# NG2093_CAM_4Lane.net
KiCad netlist of a schematic drawn in Altium Designer
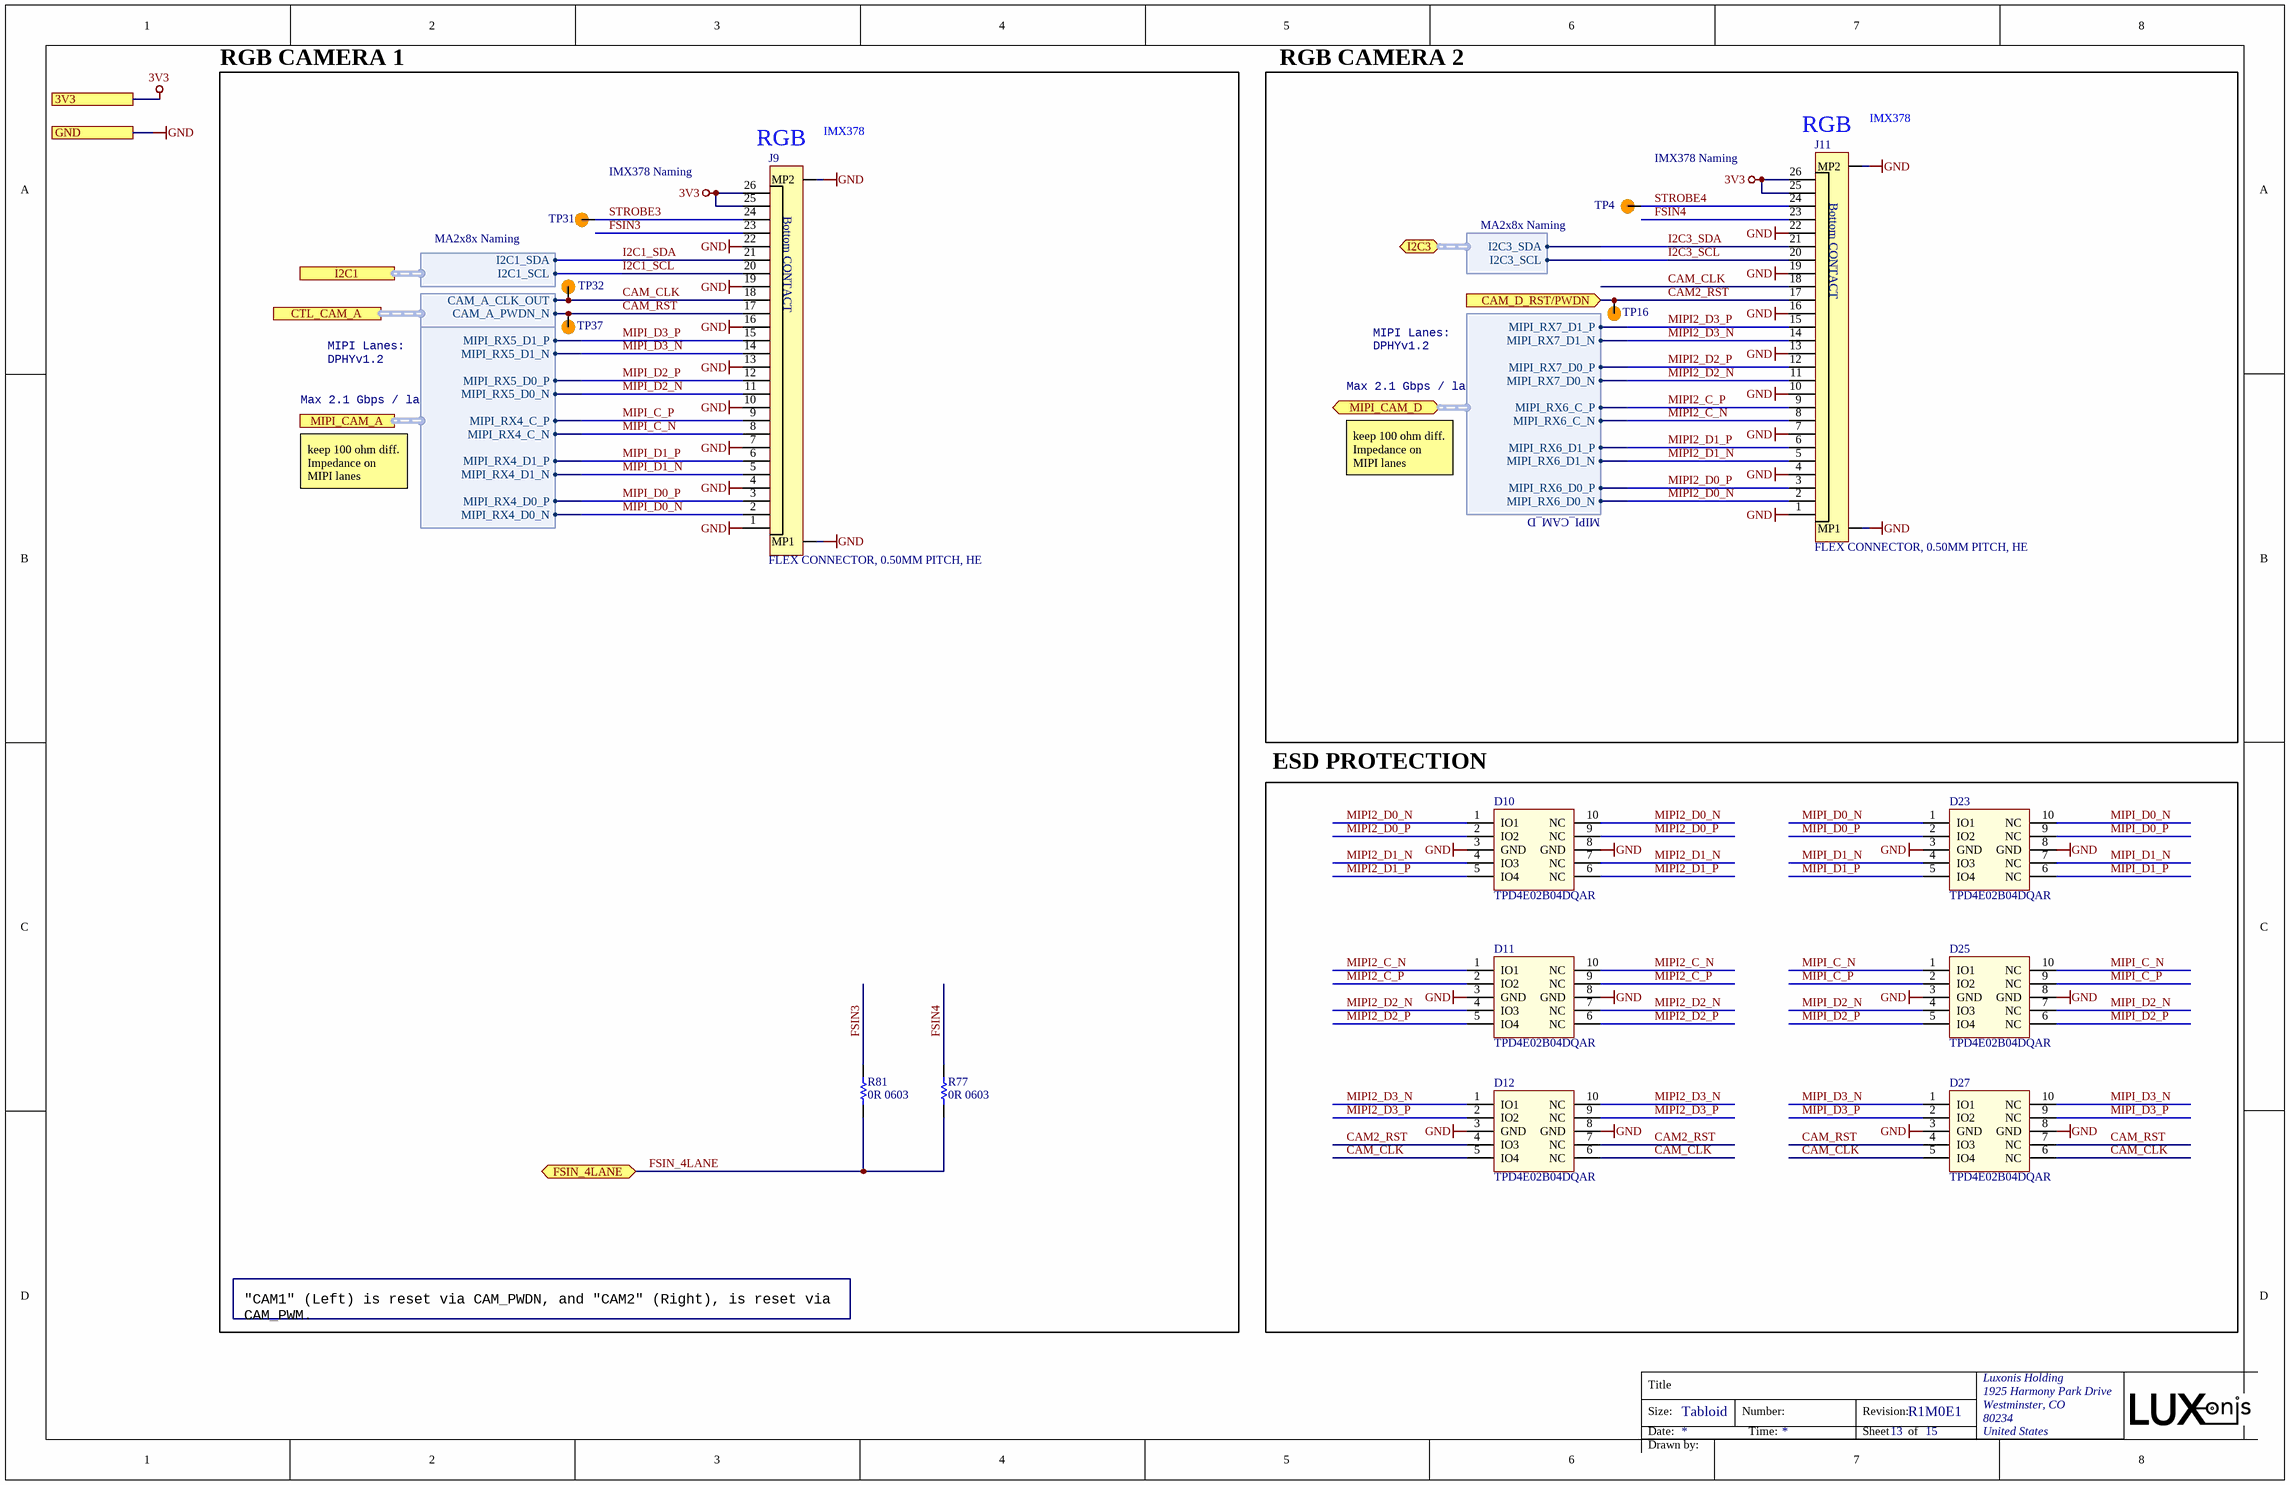
[diagram p0: NG2093_CAM_4Lane.SchDoc]

(export (version "E")
  (design (tool "Eeschema 10.0.6"))
  (components
    (comp (ref "D10")
      (value "TPD4E02B04DQAR")
      (footprint "TPD4E02B04DQAR")
      (libsource (lib "LuxonisMaster") (part "TPD4E02B04DQAR"))
    )
    (comp (ref "D11")
      (value "TPD4E02B04DQAR")
      (footprint "TPD4E02B04DQAR")
      (libsource (lib "LuxonisMaster") (part "TPD4E02B04DQAR"))
    )
    (comp (ref "D12")
      (value "TPD4E02B04DQAR")
      (footprint "TPD4E02B04DQAR")
      (libsource (lib "LuxonisMaster") (part "TPD4E02B04DQAR"))
    )
    (comp (ref "D23")
      (value "TPD4E02B04DQAR")
      (footprint "TPD4E02B04DQAR")
      (libsource (lib "LuxonisMaster") (part "TPD4E02B04DQAR"))
    )
    (comp (ref "D25")
      (value "TPD4E02B04DQAR")
      (footprint "TPD4E02B04DQAR")
      (libsource (lib "LuxonisMaster") (part "TPD4E02B04DQAR"))
    )
    (comp (ref "D27")
      (value "TPD4E02B04DQAR")
      (footprint "TPD4E02B04DQAR")
      (libsource (lib "LuxonisMaster") (part "TPD4E02B04DQAR"))
    )
    (comp (ref "J9")
      (value "FLEX CONNECTOR, 0.50MM PITCH, HE")
      (footprint "DM1090FFC:F32R-1A7H1-11026")
      (description "26 Position FFC, FPC Connector Contacts, Bottom 0.020\" (0.50mm) Surface Mount, Right Angle")
      (libsource (lib "DM1090FFC") (part "F32R-1A7H1-11026"))
    )
    (comp (ref "J11")
      (value "FLEX CONNECTOR, 0.50MM PITCH, HE")
      (footprint "DM1090FFC:F32R-1A7H1-11026")
      (description "26 Position FFC, FPC Connector Contacts, Bottom 0.020\" (0.50mm) Surface Mount, Right Angle")
      (libsource (lib "DM1090FFC") (part "F32R-1A7H1-11026"))
    )
    (comp (ref "R77")
      (value "0R 0603")
      (footprint "RESC0603(1608)_N")
      (fields (field (name "TOLERANCE") "5%"))
      (libsource (lib "LuxonisMaster") (part "CRCW06030000Z0EA"))
    )
    (comp (ref "R81")
      (value "0R 0603")
      (footprint "RESC0603(1608)_N")
      (fields (field (name "TOLERANCE") "5%"))
      (libsource (lib "LuxonisMaster") (part "CRCW06030000Z0EA"))
    )
    (comp (ref "TP4")
      (value "TP100_200_NS")
      (footprint "TP100_200_NS")
      (libsource (lib "LuxonisMaster") (part "TEST_POINT"))
    )
    (comp (ref "TP16")
      (value "TP100_200_NS")
      (footprint "TP100_200_NS")
      (libsource (lib "LuxonisMaster") (part "TEST_POINT"))
    )
    (comp (ref "TP31")
      (value "TP100_200_NS")
      (footprint "TP100_200_NS")
      (libsource (lib "LuxonisMaster") (part "TEST_POINT"))
    )
    (comp (ref "TP32")
      (value "TP100_200_NS")
      (footprint "TP100_200_NS")
      (libsource (lib "LuxonisMaster") (part "TEST_POINT"))
    )
    (comp (ref "TP37")
      (value "TP100_200_NS")
      (footprint "TP100_200_NS")
      (libsource (lib "LuxonisMaster") (part "TEST_POINT"))
    )
  )
  (nets
    (net (code "6") (name "/CAM2_RST") (class "Default")
      (node (ref "D12") (pin "4") (pinfunction "IO3_4") (pintype "passive"))
      (node (ref "D12") (pin "7") (pinfunction "NC_7") (pintype "passive"))
      (node (ref "J11") (pin "17") (pinfunction "17_17") (pintype "passive"))
      (node (ref "TP16") (pin "1") (pintype "passive"))
    )
    (net (code "7") (name "/CAM_CLK") (class "Default")
      (node (ref "D12") (pin "5") (pinfunction "IO4_5") (pintype "passive"))
      (node (ref "D12") (pin "6") (pinfunction "NC_6") (pintype "passive"))
      (node (ref "D27") (pin "5") (pinfunction "IO4_5") (pintype "passive"))
      (node (ref "D27") (pin "6") (pinfunction "NC_6") (pintype "passive"))
      (node (ref "J11") (pin "18") (pinfunction "18_18") (pintype "passive"))
      (node (ref "J9") (pin "18") (pinfunction "18_18") (pintype "passive"))
      (node (ref "TP32") (pin "1") (pintype "passive"))
    )
    (net (code "8") (name "/CAM_RST") (class "Default")
      (node (ref "D27") (pin "4") (pinfunction "IO3_4") (pintype "passive"))
      (node (ref "D27") (pin "7") (pinfunction "NC_7") (pintype "passive"))
      (node (ref "J9") (pin "17") (pinfunction "17_17") (pintype "passive"))
      (node (ref "TP37") (pin "1") (pintype "passive"))
    )
    (net (code "10") (name "/FSIN3") (class "Default")
      (node (ref "J9") (pin "23") (pinfunction "23_23") (pintype "passive"))
      (node (ref "R81") (pin "2") (pinfunction "2_2") (pintype "passive"))
    )
    (net (code "11") (name "/FSIN4") (class "Default")
      (node (ref "J11") (pin "23") (pinfunction "23_23") (pintype "passive"))
      (node (ref "R77") (pin "2") (pinfunction "2_2") (pintype "passive"))
    )
    (net (code "12") (name "/FSIN_4LANE") (class "Default")
      (node (ref "R77") (pin "1") (pinfunction "1_1") (pintype "passive"))
      (node (ref "R81") (pin "1") (pinfunction "1_1") (pintype "passive"))
    )
    (net (code "13") (name "/I2C1_SCL") (class "Default")
      (node (ref "J9") (pin "20") (pinfunction "20_20") (pintype "passive"))
    )
    (net (code "14") (name "/I2C1_SDA") (class "Default")
      (node (ref "J9") (pin "21") (pinfunction "21_21") (pintype "passive"))
    )
    (net (code "16") (name "/I2C3_SCL") (class "Default")
      (node (ref "J11") (pin "20") (pinfunction "20_20") (pintype "passive"))
    )
    (net (code "17") (name "/I2C3_SDA") (class "Default")
      (node (ref "J11") (pin "21") (pinfunction "21_21") (pintype "passive"))
    )
    (net (code "18") (name "/MIPI2_C_N") (class "Default")
      (node (ref "D11") (pin "1") (pinfunction "IO1_1") (pintype "passive"))
      (node (ref "D11") (pin "10") (pinfunction "NC_10") (pintype "passive"))
      (node (ref "J11") (pin "8") (pinfunction "8_8") (pintype "passive"))
    )
    (net (code "19") (name "/MIPI2_C_P") (class "Default")
      (node (ref "D11") (pin "2") (pinfunction "IO2_2") (pintype "passive"))
      (node (ref "D11") (pin "9") (pinfunction "NC_9") (pintype "passive"))
      (node (ref "J11") (pin "9") (pinfunction "9_9") (pintype "passive"))
    )
    (net (code "20") (name "/MIPI2_D0_N") (class "Default")
      (node (ref "D10") (pin "1") (pinfunction "IO1_1") (pintype "passive"))
      (node (ref "D10") (pin "10") (pinfunction "NC_10") (pintype "passive"))
      (node (ref "J11") (pin "2") (pinfunction "2_2") (pintype "passive"))
    )
    (net (code "21") (name "/MIPI2_D0_P") (class "Default")
      (node (ref "D10") (pin "2") (pinfunction "IO2_2") (pintype "passive"))
      (node (ref "D10") (pin "9") (pinfunction "NC_9") (pintype "passive"))
      (node (ref "J11") (pin "3") (pinfunction "3_3") (pintype "passive"))
    )
    (net (code "22") (name "/MIPI2_D1_N") (class "Default")
      (node (ref "D10") (pin "4") (pinfunction "IO3_4") (pintype "passive"))
      (node (ref "D10") (pin "7") (pinfunction "NC_7") (pintype "passive"))
      (node (ref "J11") (pin "5") (pinfunction "5_5") (pintype "passive"))
    )
    (net (code "23") (name "/MIPI2_D1_P") (class "Default")
      (node (ref "D10") (pin "5") (pinfunction "IO4_5") (pintype "passive"))
      (node (ref "D10") (pin "6") (pinfunction "NC_6") (pintype "passive"))
      (node (ref "J11") (pin "6") (pinfunction "6_6") (pintype "passive"))
    )
    (net (code "24") (name "/MIPI2_D2_N") (class "Default")
      (node (ref "D11") (pin "4") (pinfunction "IO3_4") (pintype "passive"))
      (node (ref "D11") (pin "7") (pinfunction "NC_7") (pintype "passive"))
      (node (ref "J11") (pin "11") (pinfunction "11_11") (pintype "passive"))
    )
    (net (code "25") (name "/MIPI2_D2_P") (class "Default")
      (node (ref "D11") (pin "5") (pinfunction "IO4_5") (pintype "passive"))
      (node (ref "D11") (pin "6") (pinfunction "NC_6") (pintype "passive"))
      (node (ref "J11") (pin "12") (pinfunction "12_12") (pintype "passive"))
    )
    (net (code "26") (name "/MIPI2_D3_N") (class "Default")
      (node (ref "D12") (pin "1") (pinfunction "IO1_1") (pintype "passive"))
      (node (ref "D12") (pin "10") (pinfunction "NC_10") (pintype "passive"))
      (node (ref "J11") (pin "14") (pinfunction "14_14") (pintype "passive"))
    )
    (net (code "27") (name "/MIPI2_D3_P") (class "Default")
      (node (ref "D12") (pin "2") (pinfunction "IO2_2") (pintype "passive"))
      (node (ref "D12") (pin "9") (pinfunction "NC_9") (pintype "passive"))
      (node (ref "J11") (pin "15") (pinfunction "15_15") (pintype "passive"))
    )
    (net (code "28") (name "/MIPI_C_N") (class "Default")
      (node (ref "D25") (pin "1") (pinfunction "IO1_1") (pintype "passive"))
      (node (ref "D25") (pin "10") (pinfunction "NC_10") (pintype "passive"))
      (node (ref "J9") (pin "8") (pinfunction "8_8") (pintype "passive"))
    )
    (net (code "29") (name "/MIPI_C_P") (class "Default")
      (node (ref "D25") (pin "2") (pinfunction "IO2_2") (pintype "passive"))
      (node (ref "D25") (pin "9") (pinfunction "NC_9") (pintype "passive"))
      (node (ref "J9") (pin "9") (pinfunction "9_9") (pintype "passive"))
    )
    (net (code "30") (name "/MIPI_D0_N") (class "Default")
      (node (ref "D23") (pin "1") (pinfunction "IO1_1") (pintype "passive"))
      (node (ref "D23") (pin "10") (pinfunction "NC_10") (pintype "passive"))
      (node (ref "J9") (pin "2") (pinfunction "2_2") (pintype "passive"))
    )
    (net (code "31") (name "/MIPI_D0_P") (class "Default")
      (node (ref "D23") (pin "2") (pinfunction "IO2_2") (pintype "passive"))
      (node (ref "D23") (pin "9") (pinfunction "NC_9") (pintype "passive"))
      (node (ref "J9") (pin "3") (pinfunction "3_3") (pintype "passive"))
    )
    (net (code "32") (name "/MIPI_D1_N") (class "Default")
      (node (ref "D23") (pin "4") (pinfunction "IO3_4") (pintype "passive"))
      (node (ref "D23") (pin "7") (pinfunction "NC_7") (pintype "passive"))
      (node (ref "J9") (pin "5") (pinfunction "5_5") (pintype "passive"))
    )
    (net (code "33") (name "/MIPI_D1_P") (class "Default")
      (node (ref "D23") (pin "5") (pinfunction "IO4_5") (pintype "passive"))
      (node (ref "D23") (pin "6") (pinfunction "NC_6") (pintype "passive"))
      (node (ref "J9") (pin "6") (pinfunction "6_6") (pintype "passive"))
    )
    (net (code "34") (name "/MIPI_D2_N") (class "Default")
      (node (ref "D25") (pin "4") (pinfunction "IO3_4") (pintype "passive"))
      (node (ref "D25") (pin "7") (pinfunction "NC_7") (pintype "passive"))
      (node (ref "J9") (pin "11") (pinfunction "11_11") (pintype "passive"))
    )
    (net (code "35") (name "/MIPI_D2_P") (class "Default")
      (node (ref "D25") (pin "5") (pinfunction "IO4_5") (pintype "passive"))
      (node (ref "D25") (pin "6") (pinfunction "NC_6") (pintype "passive"))
      (node (ref "J9") (pin "12") (pinfunction "12_12") (pintype "passive"))
    )
    (net (code "36") (name "/MIPI_D3_N") (class "Default")
      (node (ref "D27") (pin "1") (pinfunction "IO1_1") (pintype "passive"))
      (node (ref "D27") (pin "10") (pinfunction "NC_10") (pintype "passive"))
      (node (ref "J9") (pin "14") (pinfunction "14_14") (pintype "passive"))
    )
    (net (code "37") (name "/MIPI_D3_P") (class "Default")
      (node (ref "D27") (pin "2") (pinfunction "IO2_2") (pintype "passive"))
      (node (ref "D27") (pin "9") (pinfunction "NC_9") (pintype "passive"))
      (node (ref "J9") (pin "15") (pinfunction "15_15") (pintype "passive"))
    )
    (net (code "38") (name "/STROBE3") (class "Default")
      (node (ref "J9") (pin "24") (pinfunction "24_24") (pintype "passive"))
      (node (ref "TP31") (pin "1") (pintype "passive"))
    )
    (net (code "39") (name "/STROBE4") (class "Default")
      (node (ref "J11") (pin "24") (pinfunction "24_24") (pintype "passive"))
      (node (ref "TP4") (pin "1") (pintype "passive"))
    )
    (net (code "43") (name "3V3") (class "Default")
      (node (ref "J11") (pin "25") (pinfunction "25_25") (pintype "passive"))
      (node (ref "J11") (pin "26") (pinfunction "26_26") (pintype "passive"))
      (node (ref "J9") (pin "25") (pinfunction "25_25") (pintype "passive"))
      (node (ref "J9") (pin "26") (pinfunction "26_26") (pintype "passive"))
    )
    (net (code "44") (name "GND") (class "Default")
      (node (ref "D10") (pin "3") (pinfunction "GND_3") (pintype "passive"))
      (node (ref "D10") (pin "8") (pinfunction "GND_8") (pintype "passive"))
      (node (ref "D11") (pin "3") (pinfunction "GND_3") (pintype "passive"))
      (node (ref "D11") (pin "8") (pinfunction "GND_8") (pintype "passive"))
      (node (ref "D12") (pin "3") (pinfunction "GND_3") (pintype "passive"))
      (node (ref "D12") (pin "8") (pinfunction "GND_8") (pintype "passive"))
      (node (ref "D23") (pin "3") (pinfunction "GND_3") (pintype "passive"))
      (node (ref "D23") (pin "8") (pinfunction "GND_8") (pintype "passive"))
      (node (ref "D25") (pin "3") (pinfunction "GND_3") (pintype "passive"))
      (node (ref "D25") (pin "8") (pinfunction "GND_8") (pintype "passive"))
      (node (ref "D27") (pin "3") (pinfunction "GND_3") (pintype "passive"))
      (node (ref "D27") (pin "8") (pinfunction "GND_8") (pintype "passive"))
      (node (ref "J11") (pin "1") (pinfunction "1_1") (pintype "passive"))
      (node (ref "J11") (pin "10") (pinfunction "10_10") (pintype "passive"))
      (node (ref "J11") (pin "13") (pinfunction "13_13") (pintype "passive"))
      (node (ref "J11") (pin "16") (pinfunction "16_16") (pintype "passive"))
      (node (ref "J11") (pin "19") (pinfunction "19_19") (pintype "passive"))
      (node (ref "J11") (pin "22") (pinfunction "22_22") (pintype "passive"))
      (node (ref "J11") (pin "4") (pinfunction "4_4") (pintype "passive"))
      (node (ref "J11") (pin "7") (pinfunction "7_7") (pintype "passive"))
      (node (ref "J11") (pin "MP1") (pinfunction "MP1_MP1") (pintype "passive"))
      (node (ref "J11") (pin "MP2") (pinfunction "MP2_MP2") (pintype "passive"))
      (node (ref "J9") (pin "1") (pinfunction "1_1") (pintype "passive"))
      (node (ref "J9") (pin "10") (pinfunction "10_10") (pintype "passive"))
      (node (ref "J9") (pin "13") (pinfunction "13_13") (pintype "passive"))
      (node (ref "J9") (pin "16") (pinfunction "16_16") (pintype "passive"))
      (node (ref "J9") (pin "19") (pinfunction "19_19") (pintype "passive"))
      (node (ref "J9") (pin "22") (pinfunction "22_22") (pintype "passive"))
      (node (ref "J9") (pin "4") (pinfunction "4_4") (pintype "passive"))
      (node (ref "J9") (pin "7") (pinfunction "7_7") (pintype "passive"))
      (node (ref "J9") (pin "MP1") (pinfunction "MP1_MP1") (pintype "passive"))
      (node (ref "J9") (pin "MP2") (pinfunction "MP2_MP2") (pintype "passive"))
    )
  )
)
